# PulseOxi.net
KiCad netlist of a schematic drawn in EAGLE
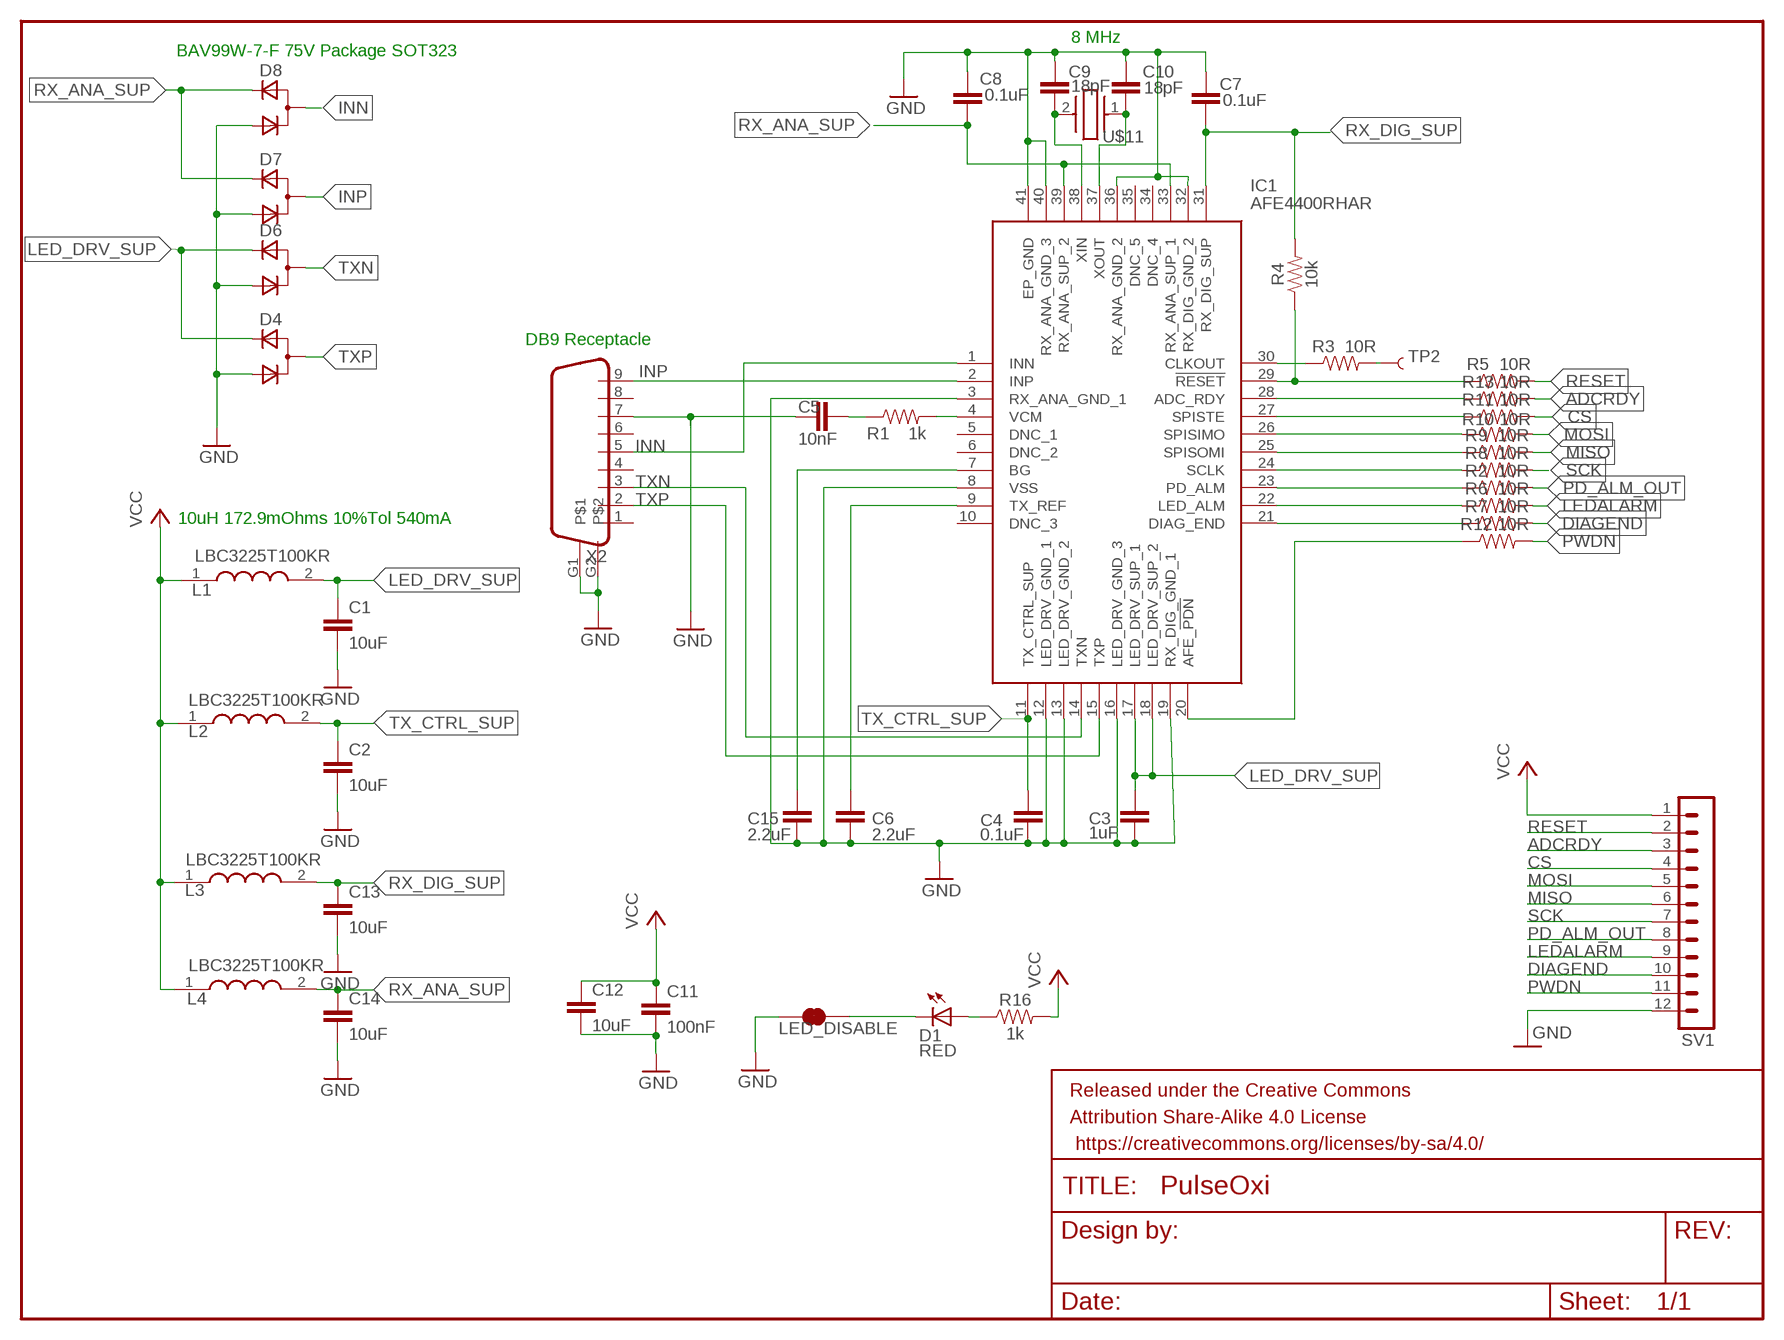
[diagram p0: schematic, sheet 1]

(export (version "E")
  (design (tool "Eeschema 10.0.6"))
  (components
    (comp (ref "C1")
      (value "10uF")
      (footprint "eagle-import:0603")
      (libsource (lib "eagle-import") (part "27PF-0603-50V-5%"))
    )
    (comp (ref "C2")
      (value "10uF")
      (footprint "eagle-import:0603")
      (libsource (lib "eagle-import") (part "27PF-0603-50V-5%"))
    )
    (comp (ref "C3")
      (value "1uF")
      (footprint "eagle-import:0603")
      (libsource (lib "eagle-import") (part "27PF-0603-50V-5%"))
    )
    (comp (ref "C4")
      (value "0.1uF")
      (footprint "eagle-import:0603")
      (libsource (lib "eagle-import") (part "27PF-0603-50V-5%"))
    )
    (comp (ref "C5")
      (value "10nF")
      (footprint "eagle-import:0603")
      (libsource (lib "eagle-import") (part "10NF-0603-50V-10%"))
    )
    (comp (ref "C6")
      (value "2.2uF")
      (footprint "eagle-import:0603")
      (libsource (lib "eagle-import") (part "27PF-0603-50V-5%"))
    )
    (comp (ref "C7")
      (value "0.1uF")
      (footprint "eagle-import:0603")
      (libsource (lib "eagle-import") (part "27PF-0603-50V-5%"))
    )
    (comp (ref "C8")
      (value "0.1uF")
      (footprint "eagle-import:0603")
      (libsource (lib "eagle-import") (part "27PF-0603-50V-5%"))
    )
    (comp (ref "C9")
      (value "18pF")
      (footprint "eagle-import:0603")
      (libsource (lib "eagle-import") (part "18PF-0603-50V-5%"))
    )
    (comp (ref "C10")
      (value "18pF")
      (footprint "eagle-import:0603")
      (libsource (lib "eagle-import") (part "18PF-0603-50V-5%"))
    )
    (comp (ref "C11")
      (value "100nF")
      (footprint "eagle-import:0603")
      (libsource (lib "eagle-import") (part "27PF-0603-50V-5%"))
    )
    (comp (ref "C12")
      (value "10uF")
      (footprint "eagle-import:0603")
      (libsource (lib "eagle-import") (part "27PF-0603-50V-5%"))
    )
    (comp (ref "C13")
      (value "10uF")
      (footprint "eagle-import:0603")
      (libsource (lib "eagle-import") (part "27PF-0603-50V-5%"))
    )
    (comp (ref "C14")
      (value "10uF")
      (footprint "eagle-import:0603")
      (libsource (lib "eagle-import") (part "27PF-0603-50V-5%"))
    )
    (comp (ref "C15")
      (value "2.2uF")
      (footprint "eagle-import:0603")
      (libsource (lib "eagle-import") (part "27PF-0603-50V-5%"))
    )
    (comp (ref "D1")
      (value "RED")
      (footprint "eagle-import:LED-0603")
      (libsource (lib "eagle-import") (part "LED-RED0603"))
    )
    (comp (ref "D4")
      (value "D_ACACSOT323")
      (footprint "eagle-import:SOT323")
      (libsource (lib "eagle-import") (part "D_ACACSOT323"))
    )
    (comp (ref "D6")
      (value "D_ACACSOT323")
      (footprint "eagle-import:SOT323")
      (libsource (lib "eagle-import") (part "D_ACACSOT323"))
    )
    (comp (ref "D7")
      (value "D_ACACSOT323")
      (footprint "eagle-import:SOT323")
      (libsource (lib "eagle-import") (part "D_ACACSOT323"))
    )
    (comp (ref "D8")
      (value "D_ACACSOT323")
      (footprint "eagle-import:SOT323")
      (libsource (lib "eagle-import") (part "D_ACACSOT323"))
    )
    (comp (ref "FRAME1")
      (value "FRAME-LETTERNO_PACKAGE")
      (footprint "eagle-import:DUMMY")
      (fields (field (name "DESIGNER") "Nobody"))
      (libsource (lib "eagle-import") (part "FRAME-LETTERNO_PACKAGE"))
    )
    (comp (ref "IC1")
      (value "AFE4400RHAR")
      (footprint "eagle-import:QFN50P600X600X100-41N")
      (fields (field (name "MOUSER_PART_NUMBER") "595-AFE4400RHAR"))
      (libsource (lib "eagle-import") (part "AFE4400RHAR"))
    )
    (comp (ref "L1")
      (value "LBC3225T100KR")
      (footprint "eagle-import:INDC3225X270N")
      (fields (field (name "MOUSER_PART_NUMBER") "963-LBC3225T100KR"))
      (libsource (lib "eagle-import") (part "LBC3225T100KR"))
    )
    (comp (ref "L2")
      (value "LBC3225T100KR")
      (footprint "eagle-import:INDC3225X270N")
      (fields (field (name "MOUSER_PART_NUMBER") "963-LBC3225T100KR"))
      (libsource (lib "eagle-import") (part "LBC3225T100KR"))
    )
    (comp (ref "L3")
      (value "LBC3225T100KR")
      (footprint "eagle-import:INDC3225X270N")
      (fields (field (name "MOUSER_PART_NUMBER") "963-LBC3225T100KR"))
      (libsource (lib "eagle-import") (part "LBC3225T100KR"))
    )
    (comp (ref "L4")
      (value "LBC3225T100KR")
      (footprint "eagle-import:INDC3225X270N")
      (fields (field (name "MOUSER_PART_NUMBER") "963-LBC3225T100KR"))
      (libsource (lib "eagle-import") (part "LBC3225T100KR"))
    )
    (comp (ref "LED_DISABLE")
      (value "JUMPER-SMT_2_NC_TRACE_SILK")
      (footprint "eagle-import:SMT-JUMPER_2_NC_TRACE_SILK")
      (libsource (lib "eagle-import") (part "JUMPER-SMT_2_NC_TRACE_SILK"))
    )
    (comp (ref "R1")
      (value "1k")
      (footprint "eagle-import:0603")
      (libsource (lib "eagle-import") (part "1KOHM-0603-1/10W-1%"))
    )
    (comp (ref "R2")
      (value "10R")
      (footprint "eagle-import:0603")
      (libsource (lib "eagle-import") (part "1.8MOHM"))
    )
    (comp (ref "R3")
      (value "10R")
      (footprint "eagle-import:0603")
      (libsource (lib "eagle-import") (part "1.8MOHM"))
    )
    (comp (ref "R4")
      (value "10k")
      (footprint "eagle-import:0603")
      (libsource (lib "eagle-import") (part "1.8MOHM"))
    )
    (comp (ref "R5")
      (value "10R")
      (footprint "eagle-import:0603")
      (libsource (lib "eagle-import") (part "1.8MOHM"))
    )
    (comp (ref "R6")
      (value "10R")
      (footprint "eagle-import:0603")
      (libsource (lib "eagle-import") (part "1.8MOHM"))
    )
    (comp (ref "R7")
      (value "10R")
      (footprint "eagle-import:0603")
      (libsource (lib "eagle-import") (part "1.8MOHM"))
    )
    (comp (ref "R8")
      (value "10R")
      (footprint "eagle-import:0603")
      (libsource (lib "eagle-import") (part "1.8MOHM"))
    )
    (comp (ref "R9")
      (value "10R")
      (footprint "eagle-import:0603")
      (libsource (lib "eagle-import") (part "1.8MOHM"))
    )
    (comp (ref "R10")
      (value "10R")
      (footprint "eagle-import:0603")
      (libsource (lib "eagle-import") (part "1.8MOHM"))
    )
    (comp (ref "R11")
      (value "10R")
      (footprint "eagle-import:0603")
      (libsource (lib "eagle-import") (part "1.8MOHM"))
    )
    (comp (ref "R12")
      (value "10R")
      (footprint "eagle-import:0603")
      (libsource (lib "eagle-import") (part "1.8MOHM"))
    )
    (comp (ref "R13")
      (value "10R")
      (footprint "eagle-import:0603")
      (libsource (lib "eagle-import") (part "1.8MOHM"))
    )
    (comp (ref "R16")
      (value "1k")
      (footprint "eagle-import:0603")
      (libsource (lib "eagle-import") (part "1KOHM-0603-1/10W-1%"))
    )
    (comp (ref "SV1")
      (value "MA12-1")
      (footprint "eagle-import:MA12-1")
      (libsource (lib "eagle-import") (part "MA12-1"))
    )
    (comp (ref "TP2")
      (value "TEST-POINT3")
      (footprint "eagle-import:PAD.03X.03")
      (libsource (lib "eagle-import") (part "TEST-POINT3"))
    )
    (comp (ref "U$11")
      (value "ABM3-8.000MHZ-D2Y-T")
      (footprint "eagle-import:ABM3")
      (fields (field (name "MOUSER_PART_NUMBER") "815-ABM3-8-D2Y-T"))
      (libsource (lib "eagle-import") (part "ABM3-8.000MHZ-D2Y-T"))
    )
    (comp (ref "X2")
      (value "DB9")
      (footprint "eagle-import:DB9")
      (libsource (lib "eagle-import") (part "DB9"))
    )
  )
  (nets
    (net (code "1") (name "ADCRDY") (class "Default")
      (node (ref "R13") (pin "2") (pinfunction "2_2") (pintype "passive"))
      (node (ref "SV1") (pin "3") (pinfunction "3_3") (pintype "passive"))
    )
    (net (code "2") (name "CS") (class "Default")
      (node (ref "R11") (pin "2") (pinfunction "2_2") (pintype "passive"))
      (node (ref "SV1") (pin "4") (pinfunction "4_4") (pintype "passive"))
    )
    (net (code "3") (name "DIAGEND") (class "Default")
      (node (ref "R7") (pin "2") (pinfunction "2_2") (pintype "passive"))
      (node (ref "SV1") (pin "10") (pinfunction "10_10") (pintype "passive"))
    )
    (net (code "4") (name "GND") (class "Default")
      (node (ref "C1") (pin "2") (pinfunction "2_2") (pintype "passive"))
      (node (ref "C10") (pin "2") (pinfunction "2_2") (pintype "passive"))
      (node (ref "C11") (pin "2") (pinfunction "2_2") (pintype "passive"))
      (node (ref "C12") (pin "2") (pinfunction "2_2") (pintype "passive"))
      (node (ref "C13") (pin "2") (pinfunction "2_2") (pintype "passive"))
      (node (ref "C14") (pin "2") (pinfunction "2_2") (pintype "passive"))
      (node (ref "C15") (pin "2") (pinfunction "2_2") (pintype "passive"))
      (node (ref "C2") (pin "2") (pinfunction "2_2") (pintype "passive"))
      (node (ref "C3") (pin "2") (pinfunction "2_2") (pintype "passive"))
      (node (ref "C4") (pin "2") (pinfunction "2_2") (pintype "passive"))
      (node (ref "C5") (pin "2") (pinfunction "2_2") (pintype "passive"))
      (node (ref "C6") (pin "2") (pinfunction "2_2") (pintype "passive"))
      (node (ref "C7") (pin "2") (pinfunction "2_2") (pintype "passive"))
      (node (ref "C8") (pin "2") (pinfunction "2_2") (pintype "passive"))
      (node (ref "C9") (pin "2") (pinfunction "2_2") (pintype "passive"))
      (node (ref "D4") (pin "2") (pinfunction "C_2") (pintype "passive"))
      (node (ref "D6") (pin "2") (pinfunction "C_2") (pintype "passive"))
      (node (ref "D7") (pin "2") (pinfunction "C_2") (pintype "passive"))
      (node (ref "D8") (pin "2") (pinfunction "C_2") (pintype "passive"))
      (node (ref "IC1") (pin "12") (pinfunction "LED_DRV_GND_1_12") (pintype "power_in"))
      (node (ref "IC1") (pin "13") (pinfunction "LED_DRV_GND_2_13") (pintype "power_in"))
      (node (ref "IC1") (pin "16") (pinfunction "LED_DRV_GND_3_16") (pintype "power_in"))
      (node (ref "IC1") (pin "19") (pinfunction "RX_DIG_GND_1_19") (pintype "power_in"))
      (node (ref "IC1") (pin "3") (pinfunction "RX_ANA_GND_1_3") (pintype "power_in"))
      (node (ref "IC1") (pin "32") (pinfunction "RX_DIG_GND_2_32") (pintype "power_in"))
      (node (ref "IC1") (pin "36") (pinfunction "RX_ANA_GND_2_36") (pintype "power_in"))
      (node (ref "IC1") (pin "40") (pinfunction "RX_ANA_GND_3_40") (pintype "power_in"))
      (node (ref "IC1") (pin "41") (pinfunction "EP_GND_41") (pintype "power_in"))
      (node (ref "IC1") (pin "8") (pinfunction "VSS_8") (pintype "power_in"))
      (node (ref "LED_DISABLE") (pin "1") (pinfunction "1_1") (pintype "passive"))
      (node (ref "SV1") (pin "12") (pinfunction "12_12") (pintype "passive"))
      (node (ref "X2") (pin "7") (pinfunction "7_7") (pintype "passive"))
      (node (ref "X2") (pin "G1") (pinfunction "P$1_G1") (pintype "bidirectional"))
      (node (ref "X2") (pin "G2") (pinfunction "P$2_G2") (pintype "bidirectional"))
    )
    (net (code "5") (name "INN") (class "Default")
      (node (ref "D8") (pin "1") (pinfunction "CA_1") (pintype "passive"))
      (node (ref "IC1") (pin "1") (pinfunction "INN_1") (pintype "input"))
      (node (ref "X2") (pin "5") (pinfunction "5_5") (pintype "passive"))
    )
    (net (code "6") (name "INP") (class "Default")
      (node (ref "D7") (pin "1") (pinfunction "CA_1") (pintype "passive"))
      (node (ref "IC1") (pin "2") (pinfunction "INP_2") (pintype "input"))
      (node (ref "X2") (pin "9") (pinfunction "9_9") (pintype "passive"))
    )
    (net (code "7") (name "LEDALARM") (class "Default")
      (node (ref "R6") (pin "2") (pinfunction "2_2") (pintype "passive"))
      (node (ref "SV1") (pin "9") (pinfunction "9_9") (pintype "passive"))
    )
    (net (code "8") (name "LED_DRV_SUP") (class "Default")
      (node (ref "C1") (pin "1") (pinfunction "1_1") (pintype "passive"))
      (node (ref "C3") (pin "1") (pinfunction "1_1") (pintype "passive"))
      (node (ref "D4") (pin "3") (pinfunction "A_3") (pintype "passive"))
      (node (ref "D6") (pin "3") (pinfunction "A_3") (pintype "passive"))
      (node (ref "IC1") (pin "17") (pinfunction "LED_DRV_SUP_1_17") (pintype "bidirectional"))
      (node (ref "IC1") (pin "18") (pinfunction "LED_DRV_SUP_2_18") (pintype "bidirectional"))
      (node (ref "L1") (pin "2") (pinfunction "2_2") (pintype "bidirectional"))
    )
    (net (code "9") (name "MISO") (class "Default")
      (node (ref "R9") (pin "2") (pinfunction "2_2") (pintype "passive"))
      (node (ref "SV1") (pin "6") (pinfunction "6_6") (pintype "passive"))
    )
    (net (code "10") (name "MOSI") (class "Default")
      (node (ref "R10") (pin "2") (pinfunction "2_2") (pintype "passive"))
      (node (ref "SV1") (pin "5") (pinfunction "5_5") (pintype "passive"))
    )
    (net (code "11") (name "Net-(C5-Pad1)") (class "Default")
      (node (ref "C5") (pin "1") (pinfunction "1_1") (pintype "passive"))
      (node (ref "R1") (pin "1") (pinfunction "1_1") (pintype "passive"))
    )
    (net (code "12") (name "Net-(D1-PadA)") (class "Default")
      (node (ref "D1") (pin "A") (pinfunction "A_A") (pintype "passive"))
      (node (ref "R16") (pin "1") (pinfunction "1_1") (pintype "passive"))
    )
    (net (code "13") (name "Net-(D1-PadC)") (class "Default")
      (node (ref "D1") (pin "C") (pinfunction "C_C") (pintype "passive"))
      (node (ref "LED_DISABLE") (pin "2") (pinfunction "2_2") (pintype "passive"))
    )
    (net (code "14") (name "Net-(IC1-ADC_RDY)") (class "Default")
      (node (ref "IC1") (pin "28") (pinfunction "ADC_RDY_28") (pintype "bidirectional"))
      (node (ref "R13") (pin "1") (pinfunction "1_1") (pintype "passive"))
    )
    (net (code "15") (name "Net-(IC1-AFE_~{PDN})") (class "Default")
      (node (ref "IC1") (pin "20") (pinfunction "AFE_~{PDN}_20") (pintype "bidirectional"))
      (node (ref "R12") (pin "1") (pinfunction "1_1") (pintype "passive"))
    )
    (net (code "16") (name "Net-(IC1-BG)") (class "Default")
      (node (ref "C15") (pin "1") (pinfunction "1_1") (pintype "passive"))
      (node (ref "IC1") (pin "7") (pinfunction "BG_7") (pintype "bidirectional"))
    )
    (net (code "17") (name "Net-(IC1-CLKOUT)") (class "Default")
      (node (ref "IC1") (pin "30") (pinfunction "CLKOUT_30") (pintype "output"))
      (node (ref "R3") (pin "1") (pinfunction "1_1") (pintype "passive"))
    )
    (net (code "18") (name "Net-(IC1-DIAG_END)") (class "Default")
      (node (ref "IC1") (pin "21") (pinfunction "DIAG_END_21") (pintype "bidirectional"))
      (node (ref "R7") (pin "1") (pinfunction "1_1") (pintype "passive"))
    )
    (net (code "19") (name "Net-(IC1-LED_ALM)") (class "Default")
      (node (ref "IC1") (pin "22") (pinfunction "LED_ALM_22") (pintype "bidirectional"))
      (node (ref "R6") (pin "1") (pinfunction "1_1") (pintype "passive"))
    )
    (net (code "20") (name "Net-(IC1-PD_ALM)") (class "Default")
      (node (ref "IC1") (pin "23") (pinfunction "PD_ALM_23") (pintype "bidirectional"))
      (node (ref "R2") (pin "1") (pinfunction "1_1") (pintype "passive"))
    )
    (net (code "21") (name "Net-(IC1-SCLK)") (class "Default")
      (node (ref "IC1") (pin "24") (pinfunction "SCLK_24") (pintype "input"))
      (node (ref "R8") (pin "1") (pinfunction "1_1") (pintype "passive"))
    )
    (net (code "22") (name "Net-(IC1-SPISIMO)") (class "Default")
      (node (ref "IC1") (pin "26") (pinfunction "SPISIMO_26") (pintype "bidirectional"))
      (node (ref "R10") (pin "1") (pinfunction "1_1") (pintype "passive"))
    )
    (net (code "23") (name "Net-(IC1-SPISOMI)") (class "Default")
      (node (ref "IC1") (pin "25") (pinfunction "SPISOMI_25") (pintype "bidirectional"))
      (node (ref "R9") (pin "1") (pinfunction "1_1") (pintype "passive"))
    )
    (net (code "24") (name "Net-(IC1-SPISTE)") (class "Default")
      (node (ref "IC1") (pin "27") (pinfunction "SPISTE_27") (pintype "bidirectional"))
      (node (ref "R11") (pin "1") (pinfunction "1_1") (pintype "passive"))
    )
    (net (code "25") (name "Net-(IC1-TX_REF)") (class "Default")
      (node (ref "C6") (pin "1") (pinfunction "1_1") (pintype "passive"))
      (node (ref "IC1") (pin "9") (pinfunction "TX_REF_9") (pintype "input"))
    )
    (net (code "26") (name "Net-(IC1-VCM)") (class "Default")
      (node (ref "IC1") (pin "4") (pinfunction "VCM_4") (pintype "bidirectional"))
      (node (ref "R1") (pin "2") (pinfunction "2_2") (pintype "passive"))
    )
    (net (code "27") (name "Net-(IC1-XIN)") (class "Default")
      (node (ref "C9") (pin "1") (pinfunction "1_1") (pintype "passive"))
      (node (ref "IC1") (pin "38") (pinfunction "XIN_38") (pintype "input"))
      (node (ref "U$11") (pin "2") (pinfunction "2_2") (pintype "bidirectional"))
    )
    (net (code "28") (name "Net-(IC1-XOUT)") (class "Default")
      (node (ref "C10") (pin "1") (pinfunction "1_1") (pintype "passive"))
      (node (ref "IC1") (pin "37") (pinfunction "XOUT_37") (pintype "output"))
      (node (ref "U$11") (pin "1") (pinfunction "1_1") (pintype "bidirectional"))
    )
    (net (code "29") (name "Net-(IC1-~{RESET})") (class "Default")
      (node (ref "IC1") (pin "29") (pinfunction "~{RESET}_29") (pintype "bidirectional"))
      (node (ref "R4") (pin "1") (pinfunction "1_1") (pintype "passive"))
      (node (ref "R5") (pin "1") (pinfunction "1_1") (pintype "passive"))
    )
    (net (code "30") (name "Net-(TP2-1)") (class "Default")
      (node (ref "R3") (pin "2") (pinfunction "2_2") (pintype "passive"))
      (node (ref "TP2") (pin "P$1") (pinfunction "1_P$1") (pintype "bidirectional"))
    )
    (net (code "31") (name "PD_ALM_OUT") (class "Default")
      (node (ref "R2") (pin "2") (pinfunction "2_2") (pintype "passive"))
      (node (ref "SV1") (pin "8") (pinfunction "8_8") (pintype "passive"))
    )
    (net (code "32") (name "PWDN") (class "Default")
      (node (ref "R12") (pin "2") (pinfunction "2_2") (pintype "passive"))
      (node (ref "SV1") (pin "11") (pinfunction "11_11") (pintype "passive"))
    )
    (net (code "33") (name "RESET") (class "Default")
      (node (ref "R5") (pin "2") (pinfunction "2_2") (pintype "passive"))
      (node (ref "SV1") (pin "2") (pinfunction "2_2") (pintype "passive"))
    )
    (net (code "34") (name "RX_ANA_SUP") (class "Default")
      (node (ref "C14") (pin "1") (pinfunction "1_1") (pintype "passive"))
      (node (ref "C8") (pin "1") (pinfunction "1_1") (pintype "passive"))
      (node (ref "D7") (pin "3") (pinfunction "A_3") (pintype "passive"))
      (node (ref "D8") (pin "3") (pinfunction "A_3") (pintype "passive"))
      (node (ref "IC1") (pin "33") (pinfunction "RX_ANA_SUP_1_33") (pintype "bidirectional"))
      (node (ref "IC1") (pin "39") (pinfunction "RX_ANA_SUP_2_39") (pintype "bidirectional"))
      (node (ref "L4") (pin "2") (pinfunction "2_2") (pintype "bidirectional"))
    )
    (net (code "35") (name "RX_DIG_SUP") (class "Default")
      (node (ref "C13") (pin "1") (pinfunction "1_1") (pintype "passive"))
      (node (ref "C7") (pin "1") (pinfunction "1_1") (pintype "passive"))
      (node (ref "IC1") (pin "31") (pinfunction "RX_DIG_SUP_31") (pintype "bidirectional"))
      (node (ref "L3") (pin "2") (pinfunction "2_2") (pintype "bidirectional"))
      (node (ref "R4") (pin "2") (pinfunction "2_2") (pintype "passive"))
    )
    (net (code "36") (name "SCK") (class "Default")
      (node (ref "R8") (pin "2") (pinfunction "2_2") (pintype "passive"))
      (node (ref "SV1") (pin "7") (pinfunction "7_7") (pintype "passive"))
    )
    (net (code "37") (name "TXN") (class "Default")
      (node (ref "D6") (pin "1") (pinfunction "CA_1") (pintype "passive"))
      (node (ref "IC1") (pin "14") (pinfunction "TXN_14") (pintype "bidirectional"))
      (node (ref "X2") (pin "3") (pinfunction "3_3") (pintype "passive"))
    )
    (net (code "38") (name "TXP") (class "Default")
      (node (ref "D4") (pin "1") (pinfunction "CA_1") (pintype "passive"))
      (node (ref "IC1") (pin "15") (pinfunction "TXP_15") (pintype "bidirectional"))
      (node (ref "X2") (pin "2") (pinfunction "2_2") (pintype "passive"))
    )
    (net (code "39") (name "TX_CTRL_SUP") (class "Default")
      (node (ref "C2") (pin "1") (pinfunction "1_1") (pintype "passive"))
      (node (ref "C4") (pin "1") (pinfunction "1_1") (pintype "passive"))
      (node (ref "IC1") (pin "11") (pinfunction "TX_CTRL_SUP_11") (pintype "bidirectional"))
      (node (ref "L2") (pin "2") (pinfunction "2_2") (pintype "bidirectional"))
    )
    (net (code "40") (name "VCC") (class "Default")
      (node (ref "C11") (pin "1") (pinfunction "1_1") (pintype "passive"))
      (node (ref "C12") (pin "1") (pinfunction "1_1") (pintype "passive"))
      (node (ref "L1") (pin "1") (pinfunction "1_1") (pintype "bidirectional"))
      (node (ref "L2") (pin "1") (pinfunction "1_1") (pintype "bidirectional"))
      (node (ref "L3") (pin "1") (pinfunction "1_1") (pintype "bidirectional"))
      (node (ref "L4") (pin "1") (pinfunction "1_1") (pintype "bidirectional"))
      (node (ref "R16") (pin "2") (pinfunction "2_2") (pintype "passive"))
      (node (ref "SV1") (pin "1") (pinfunction "1_1") (pintype "passive"))
    )
    (net (code "41") (name "unconnected-(IC1-DNC_1-Pad5)") (class "Default")
      (node (ref "IC1") (pin "5") (pinfunction "DNC_1_5") (pintype "bidirectional"))
    )
    (net (code "42") (name "unconnected-(IC1-DNC_2-Pad6)") (class "Default")
      (node (ref "IC1") (pin "6") (pinfunction "DNC_2_6") (pintype "bidirectional"))
    )
    (net (code "43") (name "unconnected-(IC1-DNC_3-Pad10)") (class "Default")
      (node (ref "IC1") (pin "10") (pinfunction "DNC_3_10") (pintype "bidirectional"))
    )
    (net (code "44") (name "unconnected-(IC1-DNC_4-Pad34)") (class "Default")
      (node (ref "IC1") (pin "34") (pinfunction "DNC_4_34") (pintype "bidirectional"))
    )
    (net (code "45") (name "unconnected-(IC1-DNC_5-Pad35)") (class "Default")
      (node (ref "IC1") (pin "35") (pinfunction "DNC_5_35") (pintype "bidirectional"))
    )
    (net (code "46") (name "unconnected-(X2-Pad1)") (class "Default")
      (node (ref "X2") (pin "1") (pinfunction "1_1") (pintype "passive"))
    )
    (net (code "47") (name "unconnected-(X2-Pad4)") (class "Default")
      (node (ref "X2") (pin "4") (pinfunction "4_4") (pintype "passive"))
    )
    (net (code "48") (name "unconnected-(X2-Pad6)") (class "Default")
      (node (ref "X2") (pin "6") (pinfunction "6_6") (pintype "passive"))
    )
    (net (code "49") (name "unconnected-(X2-Pad8)") (class "Default")
      (node (ref "X2") (pin "8") (pinfunction "8_8") (pintype "passive"))
    )
  )
)
